# usart_irq.net
KiCad netlist of a schematic drawn in EAGLE
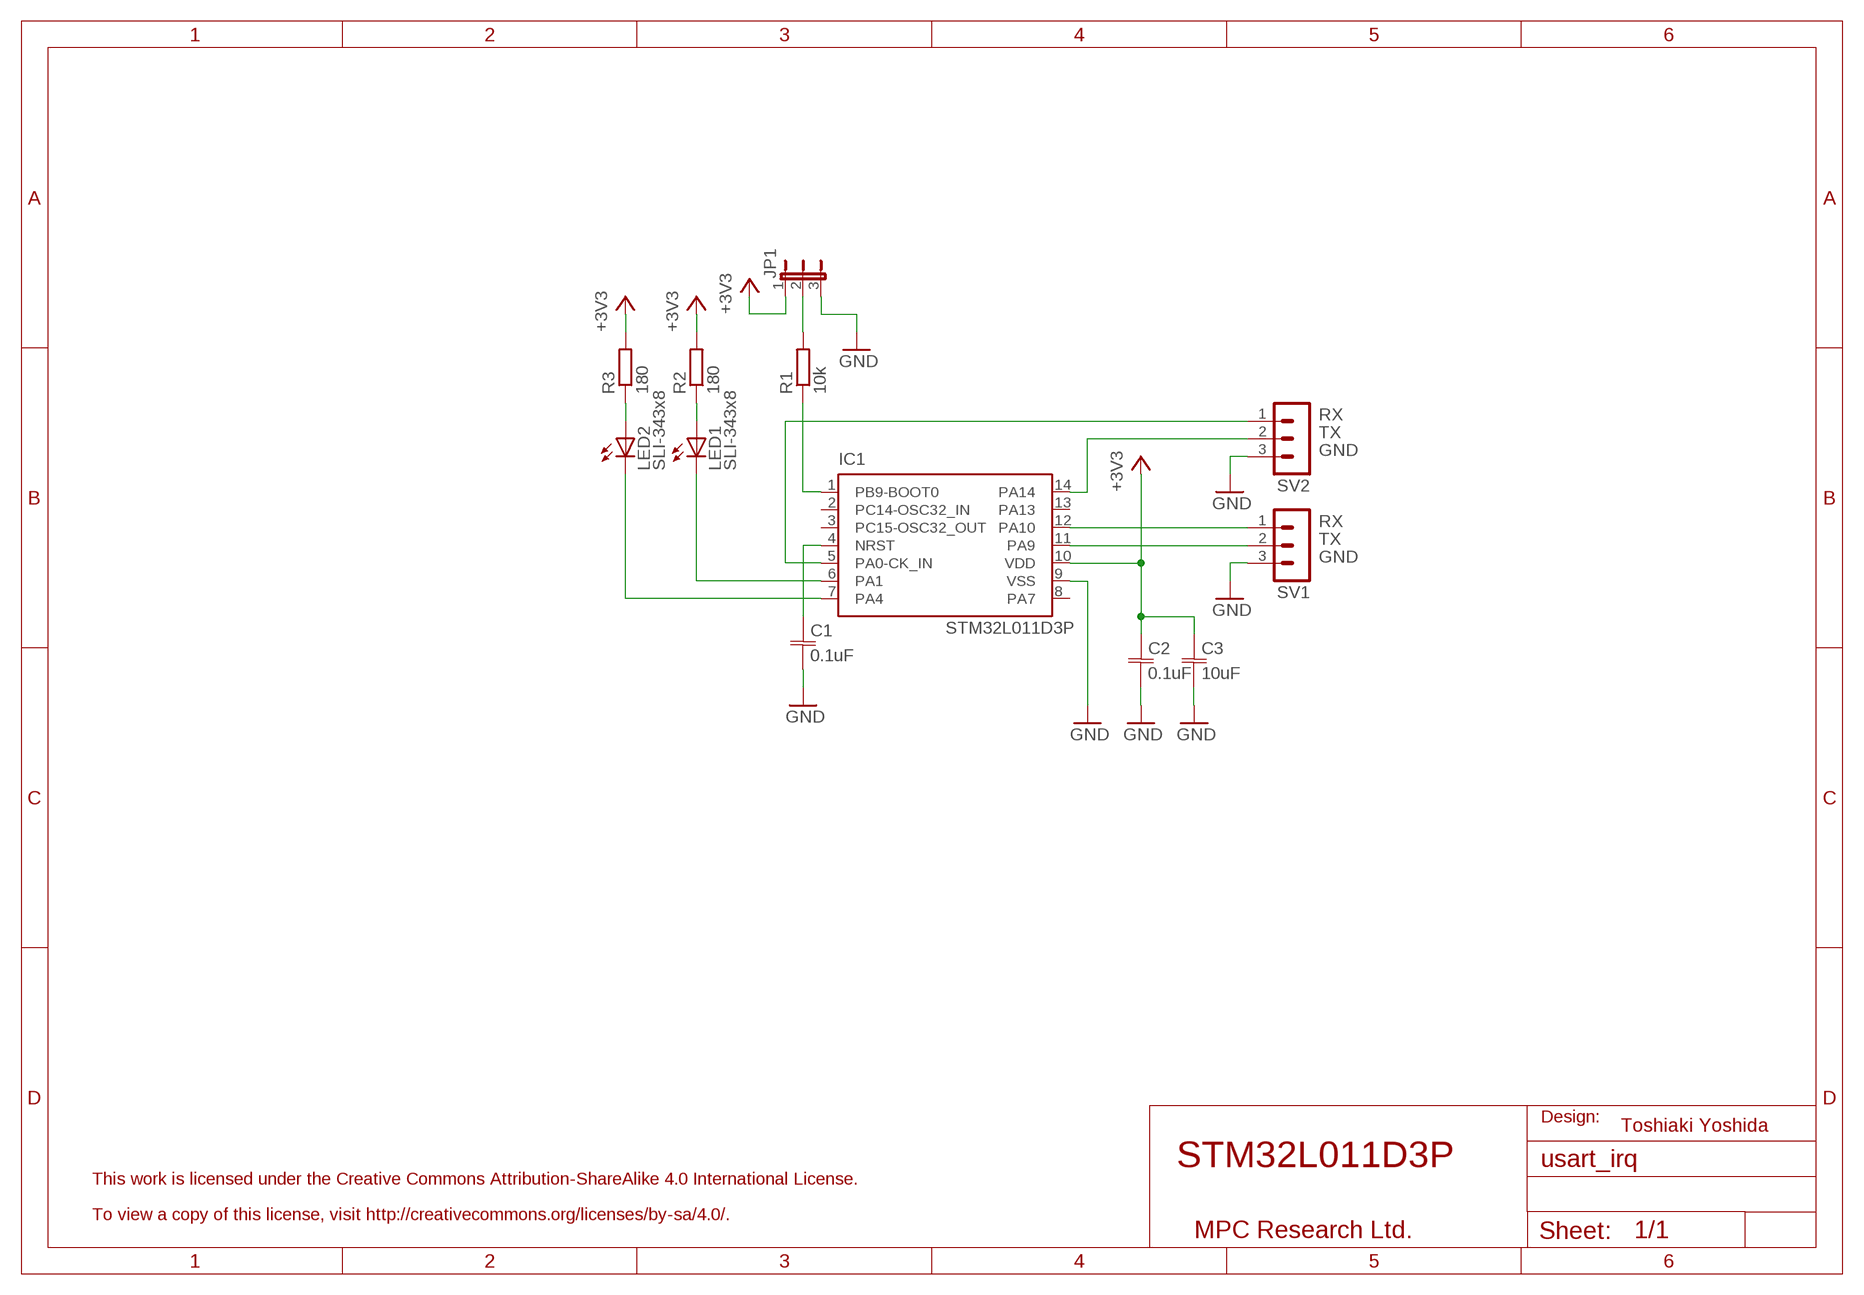
[diagram p0: schematic, sheet 1]

(export (version "E")
  (design (tool "Eeschema 10.0.6"))
  (components
    (comp (ref "C1")
      (value "0.1uF")
      (footprint "eagle-import:C050-024X044")
      (libsource (lib "eagle-import") (part "C-JIS050-024X044"))
    )
    (comp (ref "C2")
      (value "0.1uF")
      (footprint "eagle-import:C0603")
      (libsource (lib "eagle-import") (part "C-JIS0603"))
    )
    (comp (ref "C3")
      (value "10uF")
      (footprint "eagle-import:C0603")
      (libsource (lib "eagle-import") (part "C-JIS0603"))
    )
    (comp (ref "IC1")
      (value "STM32L011D3P")
      (footprint "eagle-import:TSSOP14")
      (libsource (lib "eagle-import") (part "STM32L011DP3"))
    )
    (comp (ref "JP1")
      (value "JP2E")
      (footprint "eagle-import:JP2")
      (libsource (lib "eagle-import") (part "JP2E"))
    )
    (comp (ref "LED1")
      (value "SLI-343x8")
      (footprint "eagle-import:LED3MM")
      (libsource (lib "eagle-import") (part "LED3MM"))
    )
    (comp (ref "LED2")
      (value "SLI-343x8")
      (footprint "eagle-import:LED3MM")
      (libsource (lib "eagle-import") (part "LED3MM"))
    )
    (comp (ref "R1")
      (value "10k")
      (footprint "eagle-import:0207_2V")
      (libsource (lib "eagle-import") (part "R-EU_0207/2V"))
    )
    (comp (ref "R2")
      (value "180")
      (footprint "eagle-import:0207_2V")
      (libsource (lib "eagle-import") (part "R-EU_0207/2V"))
    )
    (comp (ref "R3")
      (value "180")
      (footprint "eagle-import:0207_2V")
      (libsource (lib "eagle-import") (part "R-EU_0207/2V"))
    )
    (comp (ref "SV1")
      (value "MA03-1")
      (footprint "eagle-import:MA03-1")
      (libsource (lib "eagle-import") (part "MA03-1"))
    )
    (comp (ref "SV2")
      (value "MA03-1")
      (footprint "eagle-import:MA03-1")
      (libsource (lib "eagle-import") (part "MA03-1"))
    )
  )
  (nets
    (net (code "1") (name "+3V3") (class "Default")
      (node (ref "C2") (pin "1") (pinfunction "1_1") (pintype "passive"))
      (node (ref "C3") (pin "1") (pinfunction "1_1") (pintype "passive"))
      (node (ref "IC1") (pin "10") (pinfunction "VDD_10") (pintype "power_in"))
      (node (ref "JP1") (pin "1") (pinfunction "1_1") (pintype "passive"))
      (node (ref "R2") (pin "2") (pinfunction "2_2") (pintype "passive"))
      (node (ref "R3") (pin "2") (pinfunction "2_2") (pintype "passive"))
    )
    (net (code "2") (name "GND") (class "Default")
      (node (ref "C1") (pin "2") (pinfunction "2_2") (pintype "passive"))
      (node (ref "C2") (pin "2") (pinfunction "2_2") (pintype "passive"))
      (node (ref "C3") (pin "2") (pinfunction "2_2") (pintype "passive"))
      (node (ref "IC1") (pin "9") (pinfunction "VSS_9") (pintype "power_in"))
      (node (ref "JP1") (pin "3") (pinfunction "3_3") (pintype "passive"))
      (node (ref "SV1") (pin "3") (pinfunction "3_3") (pintype "passive"))
      (node (ref "SV2") (pin "3") (pinfunction "3_3") (pintype "passive"))
    )
    (net (code "3") (name "Net-(IC1-NRST)") (class "Default")
      (node (ref "C1") (pin "1") (pinfunction "1_1") (pintype "passive"))
      (node (ref "IC1") (pin "4") (pinfunction "NRST_4") (pintype "bidirectional"))
    )
    (net (code "4") (name "Net-(IC1-PA0-CK_IN)") (class "Default")
      (node (ref "IC1") (pin "5") (pinfunction "PA0-CK_IN_5") (pintype "bidirectional"))
      (node (ref "SV2") (pin "1") (pinfunction "1_1") (pintype "passive"))
    )
    (net (code "5") (name "Net-(IC1-PA1)") (class "Default")
      (node (ref "IC1") (pin "6") (pinfunction "PA1_6") (pintype "bidirectional"))
      (node (ref "LED1") (pin "K") (pinfunction "C_K") (pintype "passive"))
    )
    (net (code "6") (name "Net-(IC1-PA4)") (class "Default")
      (node (ref "IC1") (pin "7") (pinfunction "PA4_7") (pintype "bidirectional"))
      (node (ref "LED2") (pin "K") (pinfunction "C_K") (pintype "passive"))
    )
    (net (code "7") (name "Net-(IC1-PA9)") (class "Default")
      (node (ref "IC1") (pin "11") (pinfunction "PA9_11") (pintype "bidirectional"))
      (node (ref "SV1") (pin "2") (pinfunction "2_2") (pintype "passive"))
    )
    (net (code "8") (name "Net-(IC1-PA10)") (class "Default")
      (node (ref "IC1") (pin "12") (pinfunction "PA10_12") (pintype "bidirectional"))
      (node (ref "SV1") (pin "1") (pinfunction "1_1") (pintype "passive"))
    )
    (net (code "9") (name "Net-(IC1-PA14)") (class "Default")
      (node (ref "IC1") (pin "14") (pinfunction "PA14_14") (pintype "bidirectional"))
      (node (ref "SV2") (pin "2") (pinfunction "2_2") (pintype "passive"))
    )
    (net (code "10") (name "Net-(IC1-PB9-BOOT0)") (class "Default")
      (node (ref "IC1") (pin "1") (pinfunction "PB9-BOOT0_1") (pintype "bidirectional"))
      (node (ref "R1") (pin "1") (pinfunction "1_1") (pintype "passive"))
    )
    (net (code "11") (name "Net-(JP1-Pad2)") (class "Default")
      (node (ref "JP1") (pin "2") (pinfunction "2_2") (pintype "passive"))
      (node (ref "R1") (pin "2") (pinfunction "2_2") (pintype "passive"))
    )
    (net (code "12") (name "Net-(LED1-PadA)") (class "Default")
      (node (ref "LED1") (pin "A") (pinfunction "A_A") (pintype "passive"))
      (node (ref "R2") (pin "1") (pinfunction "1_1") (pintype "passive"))
    )
    (net (code "13") (name "Net-(LED2-PadA)") (class "Default")
      (node (ref "LED2") (pin "A") (pinfunction "A_A") (pintype "passive"))
      (node (ref "R3") (pin "1") (pinfunction "1_1") (pintype "passive"))
    )
    (net (code "14") (name "unconnected-(IC1-PA7-Pad8)") (class "Default")
      (node (ref "IC1") (pin "8") (pinfunction "PA7_8") (pintype "bidirectional"))
    )
    (net (code "15") (name "unconnected-(IC1-PA13-Pad13)") (class "Default")
      (node (ref "IC1") (pin "13") (pinfunction "PA13_13") (pintype "bidirectional"))
    )
    (net (code "16") (name "unconnected-(IC1-PC14-OSC32_IN-Pad2)") (class "Default")
      (node (ref "IC1") (pin "2") (pinfunction "PC14-OSC32_IN_2") (pintype "bidirectional"))
    )
    (net (code "17") (name "unconnected-(IC1-PC15-OSC32_OUT-Pad3)") (class "Default")
      (node (ref "IC1") (pin "3") (pinfunction "PC15-OSC32_OUT_3") (pintype "bidirectional"))
    )
  )
)
